# MIXR_Input_-_Board_to_Board_Connectors.net
KiCad netlist of a schematic drawn in Altium Designer
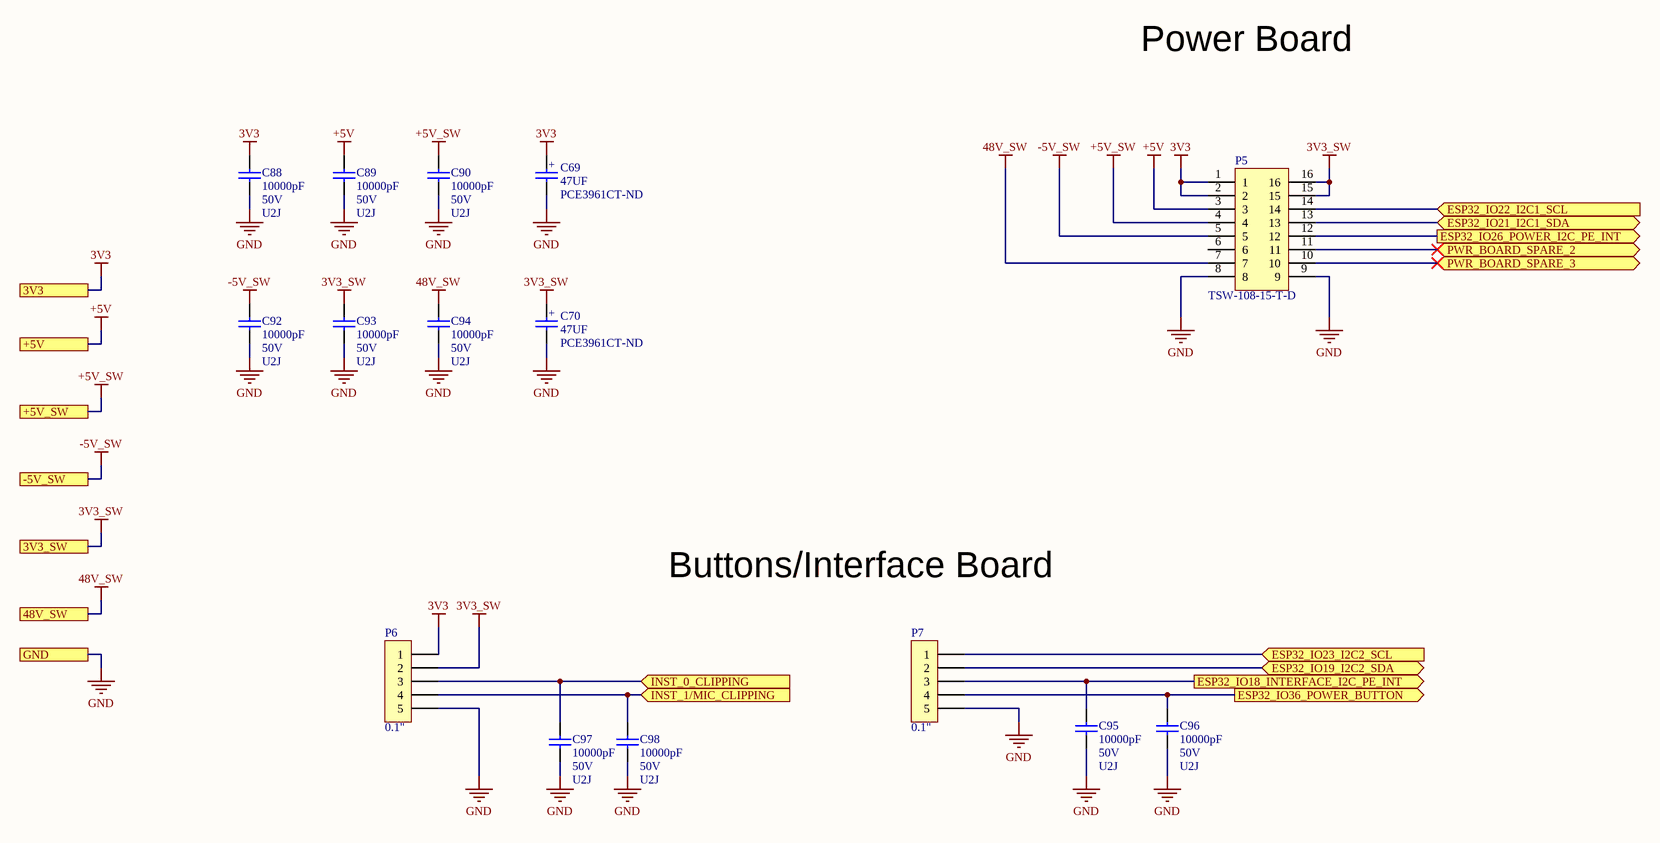
[diagram p0: MIXR Input - Board to Board Connectors.SchDoc]

(export (version "E")
  (design (tool "Eeschema 10.0.6"))
  (components
    (comp (ref "C69")
      (value "47UF")
      (footprint "CAP ALUM 6.3MM RADIAL SMD")
      (description "47µF 35V Aluminum Electrolytic Capacitors Radial, Can - SMD 1000 Hrs @ 85°C")
      (fields
        (field (name "MANUFACTURER") "Panasonic")
        (field (name "MANUFACTURER PART NUMBER") "EEE-1VA470WP")
        (field (name "SUPPLIER PART NUMBER 1") "PCE3961CT-ND")
      )
      (libsource (lib "Schematic Diagrams") (part "CAP ALUM 47UF 20% 35V SMD"))
    )
    (comp (ref "C70")
      (value "47UF")
      (footprint "CAP ALUM 6.3MM RADIAL SMD")
      (description "47µF 35V Aluminum Electrolytic Capacitors Radial, Can - SMD 1000 Hrs @ 85°C")
      (fields
        (field (name "MANUFACTURER") "Panasonic")
        (field (name "MANUFACTURER PART NUMBER") "EEE-1VA470WP")
        (field (name "SUPPLIER PART NUMBER 1") "PCE3961CT-ND")
      )
      (libsource (lib "Schematic Diagrams") (part "CAP ALUM 47UF 20% 35V SMD"))
    )
    (comp (ref "C88")
      (value "CAP CER 10nF 50V 5% X7R 0603")
      (footprint "CAP, 0603")
      (description "10000pF ±5% 50V Ceramic Capacitor U2J 0603 (1608 Metric)")
      (fields
        (field (name "TOLERANCE") "±5%")
        (field (name "CAPACITANCE") "10000pF")
        (field (name "VOLTAGE") "50V")
        (field (name "TEMPERATURE COEFFICIENT") "U2J")
      )
      (libsource (lib "Schematic Diagrams") (part "CAP CER 10nF 50V 5% X7R 0603"))
    )
    (comp (ref "C89")
      (value "CAP CER 10nF 50V 5% X7R 0603")
      (footprint "CAP, 0603")
      (description "10000pF ±5% 50V Ceramic Capacitor U2J 0603 (1608 Metric)")
      (fields
        (field (name "TOLERANCE") "±5%")
        (field (name "CAPACITANCE") "10000pF")
        (field (name "VOLTAGE") "50V")
        (field (name "TEMPERATURE COEFFICIENT") "U2J")
      )
      (libsource (lib "Schematic Diagrams") (part "CAP CER 10nF 50V 5% X7R 0603"))
    )
    (comp (ref "C90")
      (value "CAP CER 10nF 50V 5% X7R 0603")
      (footprint "CAP, 0603")
      (description "10000pF ±5% 50V Ceramic Capacitor U2J 0603 (1608 Metric)")
      (fields
        (field (name "TOLERANCE") "±5%")
        (field (name "CAPACITANCE") "10000pF")
        (field (name "VOLTAGE") "50V")
        (field (name "TEMPERATURE COEFFICIENT") "U2J")
      )
      (libsource (lib "Schematic Diagrams") (part "CAP CER 10nF 50V 5% X7R 0603"))
    )
    (comp (ref "C92")
      (value "CAP CER 10nF 50V 5% X7R 0603")
      (footprint "CAP, 0603")
      (description "10000pF ±5% 50V Ceramic Capacitor U2J 0603 (1608 Metric)")
      (fields
        (field (name "TOLERANCE") "±5%")
        (field (name "CAPACITANCE") "10000pF")
        (field (name "VOLTAGE") "50V")
        (field (name "TEMPERATURE COEFFICIENT") "U2J")
      )
      (libsource (lib "Schematic Diagrams") (part "CAP CER 10nF 50V 5% X7R 0603"))
    )
    (comp (ref "C93")
      (value "CAP CER 10nF 50V 5% X7R 0603")
      (footprint "CAP, 0603")
      (description "10000pF ±5% 50V Ceramic Capacitor U2J 0603 (1608 Metric)")
      (fields
        (field (name "TOLERANCE") "±5%")
        (field (name "CAPACITANCE") "10000pF")
        (field (name "VOLTAGE") "50V")
        (field (name "TEMPERATURE COEFFICIENT") "U2J")
      )
      (libsource (lib "Schematic Diagrams") (part "CAP CER 10nF 50V 5% X7R 0603"))
    )
    (comp (ref "C94")
      (value "CAP CER 10nF 50V 5% X7R 0603")
      (footprint "CAP, 0603")
      (description "10000pF ±5% 50V Ceramic Capacitor U2J 0603 (1608 Metric)")
      (fields
        (field (name "TOLERANCE") "±5%")
        (field (name "CAPACITANCE") "10000pF")
        (field (name "VOLTAGE") "50V")
        (field (name "TEMPERATURE COEFFICIENT") "U2J")
      )
      (libsource (lib "Schematic Diagrams") (part "CAP CER 10nF 50V 5% X7R 0603"))
    )
    (comp (ref "C95")
      (value "CAP CER 10nF 50V 5% X7R 0603")
      (footprint "CAP, 0603")
      (description "10000pF ±5% 50V Ceramic Capacitor U2J 0603 (1608 Metric)")
      (fields
        (field (name "TOLERANCE") "±5%")
        (field (name "CAPACITANCE") "10000pF")
        (field (name "VOLTAGE") "50V")
        (field (name "TEMPERATURE COEFFICIENT") "U2J")
      )
      (libsource (lib "Schematic Diagrams") (part "CAP CER 10nF 50V 5% X7R 0603"))
    )
    (comp (ref "C96")
      (value "CAP CER 10nF 50V 5% X7R 0603")
      (footprint "CAP, 0603")
      (description "10000pF ±5% 50V Ceramic Capacitor U2J 0603 (1608 Metric)")
      (fields
        (field (name "TOLERANCE") "±5%")
        (field (name "CAPACITANCE") "10000pF")
        (field (name "VOLTAGE") "50V")
        (field (name "TEMPERATURE COEFFICIENT") "U2J")
      )
      (libsource (lib "Schematic Diagrams") (part "CAP CER 10nF 50V 5% X7R 0603"))
    )
    (comp (ref "C97")
      (value "CAP CER 10nF 50V 5% X7R 0603")
      (footprint "CAP, 0603")
      (description "10000pF ±5% 50V Ceramic Capacitor U2J 0603 (1608 Metric)")
      (fields
        (field (name "TOLERANCE") "±5%")
        (field (name "CAPACITANCE") "10000pF")
        (field (name "VOLTAGE") "50V")
        (field (name "TEMPERATURE COEFFICIENT") "U2J")
      )
      (libsource (lib "Schematic Diagrams") (part "CAP CER 10nF 50V 5% X7R 0603"))
    )
    (comp (ref "C98")
      (value "CAP CER 10nF 50V 5% X7R 0603")
      (footprint "CAP, 0603")
      (description "10000pF ±5% 50V Ceramic Capacitor U2J 0603 (1608 Metric)")
      (fields
        (field (name "TOLERANCE") "±5%")
        (field (name "CAPACITANCE") "10000pF")
        (field (name "VOLTAGE") "50V")
        (field (name "TEMPERATURE COEFFICIENT") "U2J")
      )
      (libsource (lib "Schematic Diagrams") (part "CAP CER 10nF 50V 5% X7R 0603"))
    )
    (comp (ref "P5")
      (value "CONN 16POS HEADER 0.1\" 0.73\" MALE")
      (footprint "CONN, 16POS 0.100\" 0.73\" MALE")
      (fields
        (field (name "MANUFACTURER") "Samtec")
        (field (name "MANUFACTURER PART NUMBER") "TSW-108-15-T-D")
      )
      (libsource (lib "Schematic Diagrams") (part "CONN 16POS HEADER 0.1{dblquote} 0.73{dblquote} MALE"))
    )
    (comp (ref "P6")
      (value "0.1\"")
      (footprint "CONN, 5POS 1.23\" 0.100\" MALE Header")
      (description "CONN HEADER 5POS .100\" SNGL")
      (fields
        (field (name "MANUFACTURER") "Samtec")
        (field (name "MANUFACTURER PART NUMBER") "TSW-105-20-T-S")
      )
      (libsource (lib "Schematic Diagrams") (part "CONN 5POS 0.1{dblquote} 1{dblquote} MALE HEADER"))
    )
    (comp (ref "P7")
      (value "0.1\"")
      (footprint "CONN, 5POS 1.23\" 0.100\" MALE Header")
      (description "CONN HEADER 5POS .100\" SNGL")
      (fields
        (field (name "MANUFACTURER") "Samtec")
        (field (name "MANUFACTURER PART NUMBER") "TSW-105-20-T-S")
      )
      (libsource (lib "Schematic Diagrams") (part "CONN 5POS 0.1{dblquote} 1{dblquote} MALE HEADER"))
    )
  )
  (nets
    (net (code "1") (name "+5V") (class "Default")
      (node (ref "C89") (pin "1") (pinfunction "1_1") (pintype "passive"))
      (node (ref "P5") (pin "3") (pinfunction "3_3") (pintype "passive"))
    )
    (net (code "2") (name "+5V_SW") (class "Default")
      (node (ref "C90") (pin "1") (pinfunction "1_1") (pintype "passive"))
      (node (ref "P5") (pin "4") (pinfunction "4_4") (pintype "passive"))
    )
    (net (code "3") (name "-5V_SW") (class "Default")
      (node (ref "C92") (pin "1") (pinfunction "1_1") (pintype "passive"))
      (node (ref "P5") (pin "5") (pinfunction "5_5") (pintype "passive"))
    )
    (net (code "4") (name "/ESP32_IO18_INTERFACE_I2C_PE_INT") (class "Default")
      (node (ref "C95") (pin "1") (pinfunction "1_1") (pintype "passive"))
      (node (ref "P7") (pin "3") (pinfunction "3_3") (pintype "passive"))
    )
    (net (code "5") (name "/ESP32_IO19_I2C2_SDA") (class "Default")
      (node (ref "P7") (pin "2") (pinfunction "2_2") (pintype "passive"))
    )
    (net (code "6") (name "/ESP32_IO21_I2C1_SDA") (class "Default")
      (node (ref "P5") (pin "13") (pinfunction "13_13") (pintype "passive"))
    )
    (net (code "7") (name "/ESP32_IO22_I2C1_SCL") (class "Default")
      (node (ref "P5") (pin "14") (pinfunction "14_14") (pintype "passive"))
    )
    (net (code "8") (name "/ESP32_IO23_I2C2_SCL") (class "Default")
      (node (ref "P7") (pin "1") (pinfunction "1_1") (pintype "passive"))
    )
    (net (code "9") (name "/ESP32_IO26_POWER_I2C_PE_INT") (class "Default")
      (node (ref "P5") (pin "12") (pinfunction "12_12") (pintype "passive"))
    )
    (net (code "10") (name "/ESP32_IO36_POWER_BUTTON") (class "Default")
      (node (ref "C96") (pin "1") (pinfunction "1_1") (pintype "passive"))
      (node (ref "P7") (pin "4") (pinfunction "4_4") (pintype "passive"))
    )
    (net (code "11") (name "/INST_0_CLIPPING") (class "Default")
      (node (ref "C97") (pin "1") (pinfunction "1_1") (pintype "passive"))
      (node (ref "P6") (pin "3") (pinfunction "3_3") (pintype "passive"))
    )
    (net (code "12") (name "/INST_1{slash}MIC_CLIPPING") (class "Default")
      (node (ref "C98") (pin "1") (pinfunction "1_1") (pintype "passive"))
      (node (ref "P6") (pin "4") (pinfunction "4_4") (pintype "passive"))
    )
    (net (code "13") (name "/PWR_BOARD_SPARE_2") (class "Default")
      (node (ref "P5") (pin "11") (pinfunction "11_11") (pintype "passive+no_connect"))
    )
    (net (code "14") (name "/PWR_BOARD_SPARE_3") (class "Default")
      (node (ref "P5") (pin "10") (pinfunction "10_10") (pintype "passive+no_connect"))
    )
    (net (code "15") (name "3V3") (class "Default")
      (node (ref "C69") (pin "1") (pinfunction "1_1") (pintype "passive"))
      (node (ref "C88") (pin "1") (pinfunction "1_1") (pintype "passive"))
      (node (ref "P5") (pin "1") (pinfunction "1_1") (pintype "passive"))
      (node (ref "P5") (pin "2") (pinfunction "2_2") (pintype "passive"))
      (node (ref "P6") (pin "1") (pinfunction "1_1") (pintype "passive"))
    )
    (net (code "16") (name "3V3_SW") (class "Default")
      (node (ref "C70") (pin "1") (pinfunction "1_1") (pintype "passive"))
      (node (ref "C93") (pin "1") (pinfunction "1_1") (pintype "passive"))
      (node (ref "P5") (pin "15") (pinfunction "15_15") (pintype "passive"))
      (node (ref "P5") (pin "16") (pinfunction "16_16") (pintype "passive"))
      (node (ref "P6") (pin "2") (pinfunction "2_2") (pintype "passive"))
    )
    (net (code "17") (name "48V_SW") (class "Default")
      (node (ref "C94") (pin "1") (pinfunction "1_1") (pintype "passive"))
      (node (ref "P5") (pin "7") (pinfunction "7_7") (pintype "passive"))
    )
    (net (code "18") (name "GND") (class "Default")
      (node (ref "C69") (pin "2") (pinfunction "2_2") (pintype "passive"))
      (node (ref "C70") (pin "2") (pinfunction "2_2") (pintype "passive"))
      (node (ref "C88") (pin "2") (pinfunction "2_2") (pintype "passive"))
      (node (ref "C89") (pin "2") (pinfunction "2_2") (pintype "passive"))
      (node (ref "C90") (pin "2") (pinfunction "2_2") (pintype "passive"))
      (node (ref "C92") (pin "2") (pinfunction "2_2") (pintype "passive"))
      (node (ref "C93") (pin "2") (pinfunction "2_2") (pintype "passive"))
      (node (ref "C94") (pin "2") (pinfunction "2_2") (pintype "passive"))
      (node (ref "C95") (pin "2") (pinfunction "2_2") (pintype "passive"))
      (node (ref "C96") (pin "2") (pinfunction "2_2") (pintype "passive"))
      (node (ref "C97") (pin "2") (pinfunction "2_2") (pintype "passive"))
      (node (ref "C98") (pin "2") (pinfunction "2_2") (pintype "passive"))
      (node (ref "P5") (pin "8") (pinfunction "8_8") (pintype "passive"))
      (node (ref "P5") (pin "9") (pinfunction "9_9") (pintype "passive"))
      (node (ref "P6") (pin "5") (pinfunction "5_5") (pintype "passive"))
      (node (ref "P7") (pin "5") (pinfunction "5_5") (pintype "passive"))
    )
    (net (code "19") (name "unconnected-(P5-Pad6)") (class "Default")
      (node (ref "P5") (pin "6") (pinfunction "6_6") (pintype "passive"))
    )
  )
)
